# RGBstrip-ESP07-Controller-Amp-V1_2.net
KiCad netlist of a schematic drawn in EAGLE
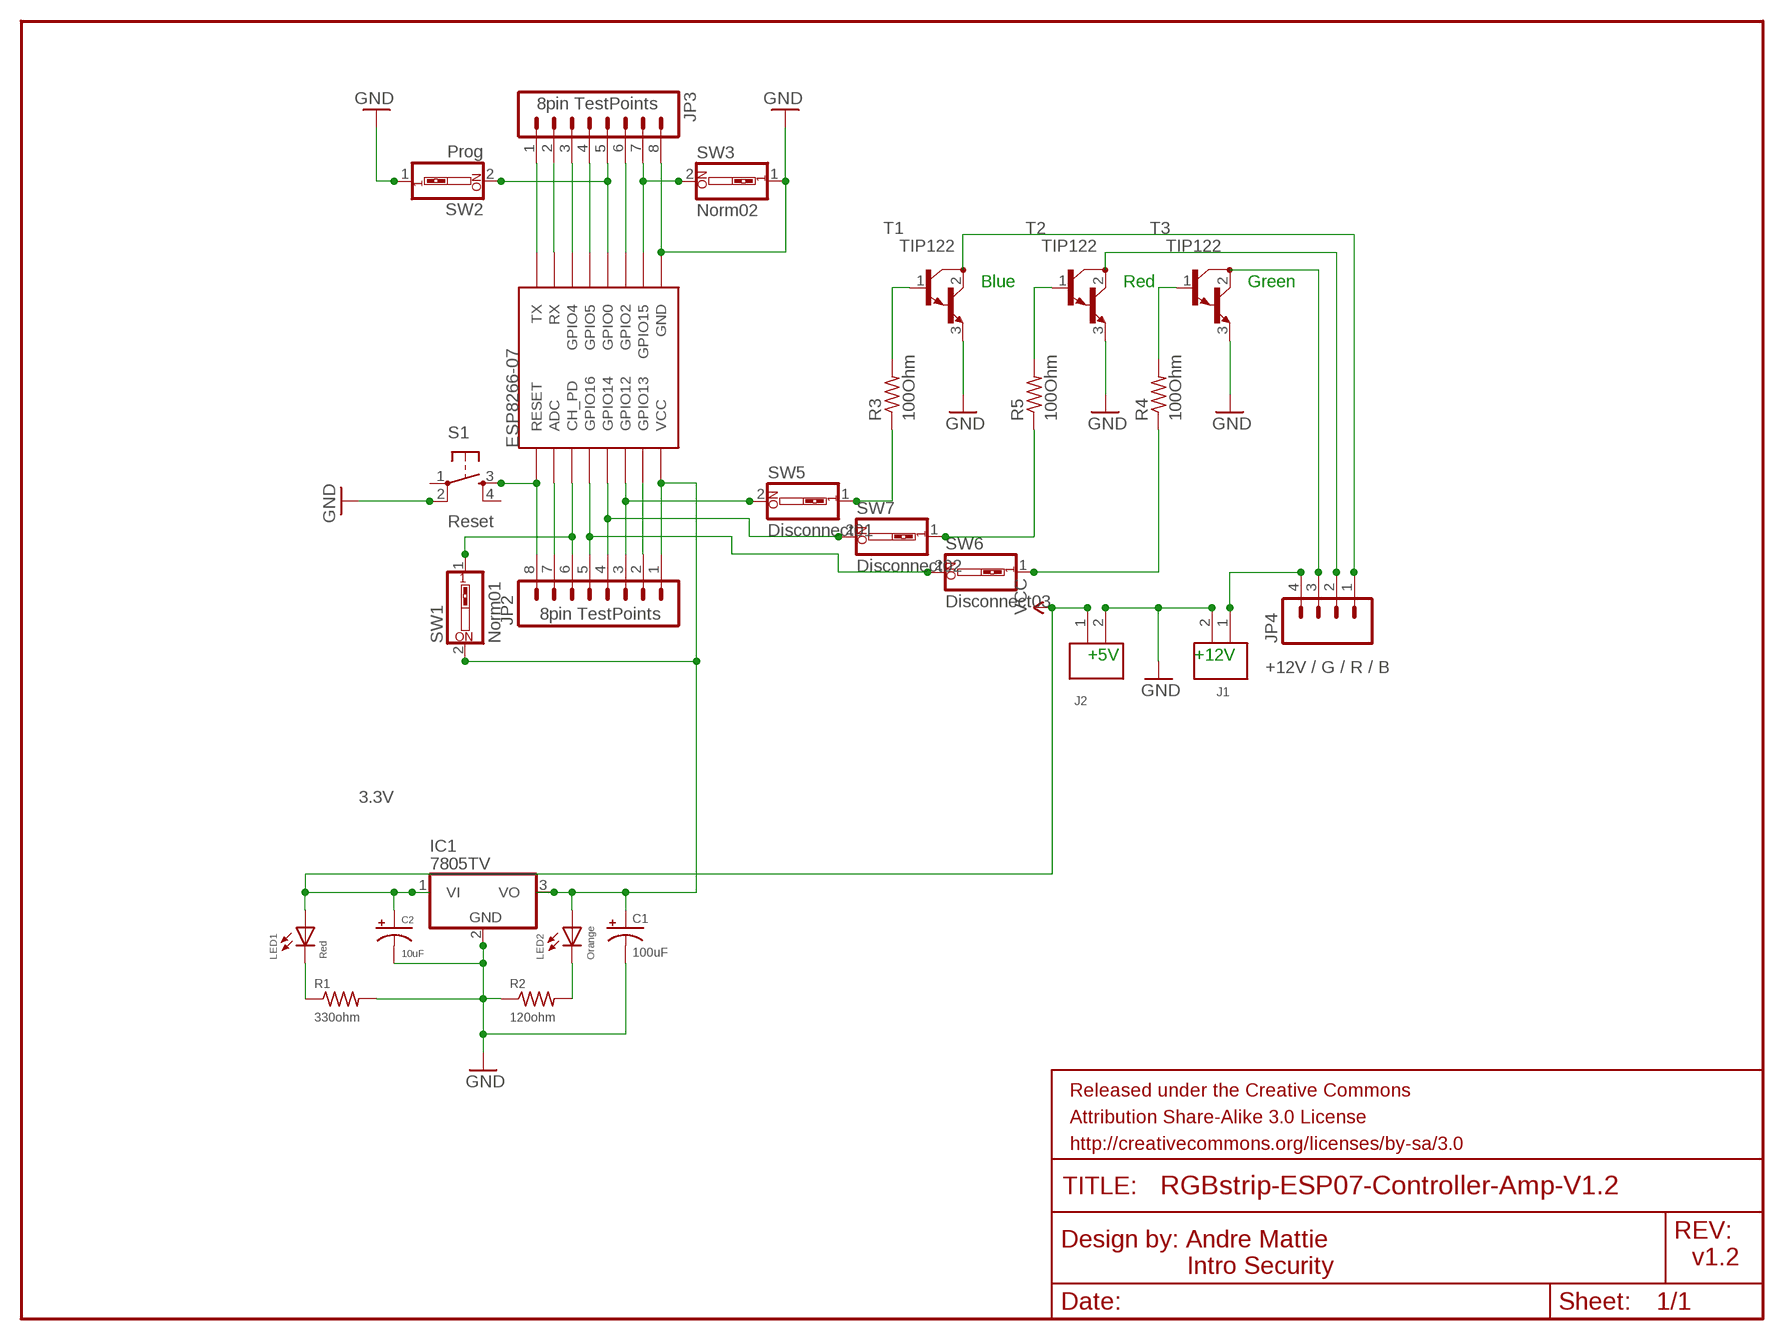
[diagram p0: schematic, sheet 1]

(export (version "E")
  (design (tool "Eeschema 10.0.6"))
  (components
    (comp (ref "C1")
      (value "100uF")
      (footprint "eagle-import:CPOL-RADIAL-100UF-25V")
      (libsource (lib "eagle-import") (part "CAP_POLPTH1"))
    )
    (comp (ref "C2")
      (value "10uF")
      (footprint "eagle-import:CPOL-RADIAL-10UF-25V")
      (libsource (lib "eagle-import") (part "CAP_POLPTH2"))
    )
    (comp (ref "ESP8266-07")
      (value "ESP07-16PINBOTTOM")
      (footprint "eagle-import:ESP07-16PIN")
      (libsource (lib "eagle-import") (part "ESP07-16PINBOTTOM"))
    )
    (comp (ref "FRAME1")
      (value "FRAME-LETTER")
      (footprint "eagle-import:CREATIVE_COMMONS")
      (libsource (lib "eagle-import") (part "FRAME-LETTER"))
    )
    (comp (ref "IC1")
      (value "7805TV")
      (footprint "eagle-import:TO220V")
      (libsource (lib "eagle-import") (part "78TV05"))
    )
    (comp (ref "J1")
      (value "SCREW-TERMINAL_2_0.100")
      (footprint "eagle-import:CONN_BLOCK_2")
      (libsource (lib "eagle-import") (part "SCREW-TERMINAL_2_0.100"))
    )
    (comp (ref "J2")
      (value "SCREW-TERMINAL_2_0.100")
      (footprint "eagle-import:CONN_BLOCK_2")
      (libsource (lib "eagle-import") (part "SCREW-TERMINAL_2_0.100"))
    )
    (comp (ref "JP2")
      (value "8pin TestPoints")
      (footprint "eagle-import:1X08_LONGPADS")
      (libsource (lib "eagle-import") (part "M08LONGPADS"))
    )
    (comp (ref "JP3")
      (value "8pin TestPoints")
      (footprint "eagle-import:1X08_LONGPADS")
      (libsource (lib "eagle-import") (part "M08LONGPADS"))
    )
    (comp (ref "JP4")
      (value "+12V / G / R / B")
      (footprint "eagle-import:1X04_LONGPADS")
      (libsource (lib "eagle-import") (part "M04LONGPADS"))
    )
    (comp (ref "LED1")
      (value "Red")
      (footprint "eagle-import:LED3MM")
      (libsource (lib "eagle-import") (part "LED3MM"))
    )
    (comp (ref "LED2")
      (value "Orange")
      (footprint "eagle-import:LED3MM")
      (libsource (lib "eagle-import") (part "LED3MM"))
    )
    (comp (ref "R1")
      (value "330ohm")
      (footprint "eagle-import:0309V")
      (libsource (lib "eagle-import") (part "R-US_0309/V"))
    )
    (comp (ref "R2")
      (value "120ohm")
      (footprint "eagle-import:0309V")
      (libsource (lib "eagle-import") (part "R-US_0309/V"))
    )
    (comp (ref "R3")
      (value "100Ohm")
      (footprint "eagle-import:0309V")
      (libsource (lib "eagle-import") (part "R-US_0309/V"))
    )
    (comp (ref "R4")
      (value "100Ohm")
      (footprint "eagle-import:0309V")
      (libsource (lib "eagle-import") (part "R-US_0309/V"))
    )
    (comp (ref "R5")
      (value "100Ohm")
      (footprint "eagle-import:0309V")
      (libsource (lib "eagle-import") (part "R-US_0309/V"))
    )
    (comp (ref "S1")
      (value "Reset")
      (footprint "eagle-import:TACTILE-PTH")
      (libsource (lib "eagle-import") (part "TAC_SWITCHPTH"))
    )
    (comp (ref "SW1")
      (value "Norm01")
      (footprint "eagle-import:EDG-01")
      (libsource (lib "eagle-import") (part "SW_DIP-1"))
    )
    (comp (ref "SW2")
      (value "Prog")
      (footprint "eagle-import:EDG-01")
      (libsource (lib "eagle-import") (part "SW_DIP-1"))
    )
    (comp (ref "SW3")
      (value "Norm02")
      (footprint "eagle-import:EDG-01")
      (libsource (lib "eagle-import") (part "SW_DIP-1"))
    )
    (comp (ref "SW5")
      (value "Disconnect01")
      (footprint "eagle-import:EDG-01")
      (libsource (lib "eagle-import") (part "SW_DIP-1"))
    )
    (comp (ref "SW6")
      (value "Disconnect03")
      (footprint "eagle-import:EDG-01")
      (libsource (lib "eagle-import") (part "SW_DIP-1"))
    )
    (comp (ref "SW7")
      (value "Disconnect02")
      (footprint "eagle-import:EDG-01")
      (libsource (lib "eagle-import") (part "SW_DIP-1"))
    )
    (comp (ref "T1")
      (value "TIP122")
      (footprint "eagle-import:TO220")
      (libsource (lib "eagle-import") (part "TIP122"))
    )
    (comp (ref "T2")
      (value "TIP122")
      (footprint "eagle-import:TO220")
      (libsource (lib "eagle-import") (part "TIP122"))
    )
    (comp (ref "T3")
      (value "TIP122")
      (footprint "eagle-import:TO220")
      (libsource (lib "eagle-import") (part "TIP122"))
    )
  )
  (nets
    (net (code "1") (name "/3.3V") (class "Default")
      (node (ref "C1") (pin "1") (pinfunction "+_1") (pintype "passive"))
      (node (ref "ESP8266-07") (pin "VCC") (pinfunction "VCC_VCC") (pintype "bidirectional"))
      (node (ref "IC1") (pin "3") (pinfunction "VO_3") (pintype "passive"))
      (node (ref "JP2") (pin "1") (pinfunction "1_1") (pintype "passive"))
      (node (ref "LED2") (pin "A") (pinfunction "A_A") (pintype "passive"))
      (node (ref "SW1") (pin "2") (pinfunction "2_2") (pintype "passive"))
    )
    (net (code "2") (name "GND") (class "Default")
      (node (ref "C1") (pin "2") (pinfunction "-_2") (pintype "passive"))
      (node (ref "C2") (pin "2") (pinfunction "-_2") (pintype "passive"))
      (node (ref "ESP8266-07") (pin "GND") (pinfunction "GND_GND") (pintype "bidirectional"))
      (node (ref "IC1") (pin "2") (pinfunction "GND_2") (pintype "passive"))
      (node (ref "J1") (pin "2") (pinfunction "2_2") (pintype "bidirectional"))
      (node (ref "J2") (pin "2") (pinfunction "2_2") (pintype "bidirectional"))
      (node (ref "JP3") (pin "8") (pinfunction "8_8") (pintype "passive"))
      (node (ref "R1") (pin "2") (pinfunction "2_2") (pintype "passive"))
      (node (ref "R2") (pin "1") (pinfunction "1_1") (pintype "passive"))
      (node (ref "S1") (pin "2") (pinfunction "2_2") (pintype "passive"))
      (node (ref "SW2") (pin "1") (pinfunction "1_1") (pintype "passive"))
      (node (ref "SW3") (pin "1") (pinfunction "1_1") (pintype "passive"))
      (node (ref "T1") (pin "3") (pinfunction "E_3") (pintype "passive"))
      (node (ref "T2") (pin "3") (pinfunction "E_3") (pintype "passive"))
      (node (ref "T3") (pin "3") (pinfunction "E_3") (pintype "passive"))
    )
    (net (code "3") (name "Net-(ESP8266-07-PadADC)") (class "Default")
      (node (ref "ESP8266-07") (pin "ADC") (pinfunction "ADC_ADC") (pintype "bidirectional"))
      (node (ref "JP2") (pin "7") (pinfunction "7_7") (pintype "passive"))
    )
    (net (code "4") (name "Net-(ESP8266-07-PadCH_PD)") (class "Default")
      (node (ref "ESP8266-07") (pin "CH_PD") (pinfunction "CH_PD_CH_PD") (pintype "bidirectional"))
      (node (ref "JP2") (pin "6") (pinfunction "6_6") (pintype "passive"))
      (node (ref "SW1") (pin "1") (pinfunction "1_1") (pintype "passive"))
    )
    (net (code "5") (name "Net-(ESP8266-07-PadGPIO0)") (class "Default")
      (node (ref "ESP8266-07") (pin "GPIO0") (pinfunction "GPIO0_GPIO0") (pintype "bidirectional"))
      (node (ref "JP3") (pin "5") (pinfunction "5_5") (pintype "passive"))
      (node (ref "SW2") (pin "2") (pinfunction "2_2") (pintype "passive"))
    )
    (net (code "6") (name "Net-(ESP8266-07-PadGPIO2)") (class "Default")
      (node (ref "ESP8266-07") (pin "GPIO2") (pinfunction "GPIO2_GPIO2") (pintype "bidirectional"))
      (node (ref "JP3") (pin "6") (pinfunction "6_6") (pintype "passive"))
    )
    (net (code "7") (name "Net-(ESP8266-07-PadGPIO4)") (class "Default")
      (node (ref "ESP8266-07") (pin "GPIO4") (pinfunction "GPIO4_GPIO4") (pintype "bidirectional"))
      (node (ref "JP3") (pin "3") (pinfunction "3_3") (pintype "passive"))
    )
    (net (code "8") (name "Net-(ESP8266-07-PadGPIO5)") (class "Default")
      (node (ref "ESP8266-07") (pin "GPIO5") (pinfunction "GPIO5_GPIO5") (pintype "bidirectional"))
      (node (ref "JP3") (pin "4") (pinfunction "4_4") (pintype "passive"))
    )
    (net (code "9") (name "Net-(ESP8266-07-PadGPIO12)") (class "Default")
      (node (ref "ESP8266-07") (pin "GPIO12") (pinfunction "GPIO12_GPIO12") (pintype "bidirectional"))
      (node (ref "JP2") (pin "3") (pinfunction "3_3") (pintype "passive"))
      (node (ref "SW5") (pin "2") (pinfunction "2_2") (pintype "passive"))
    )
    (net (code "10") (name "Net-(ESP8266-07-PadGPIO13)") (class "Default")
      (node (ref "ESP8266-07") (pin "GPIO13") (pinfunction "GPIO13_GPIO13") (pintype "bidirectional"))
      (node (ref "JP2") (pin "2") (pinfunction "2_2") (pintype "passive"))
    )
    (net (code "11") (name "Net-(ESP8266-07-PadGPIO14)") (class "Default")
      (node (ref "ESP8266-07") (pin "GPIO14") (pinfunction "GPIO14_GPIO14") (pintype "bidirectional"))
      (node (ref "JP2") (pin "4") (pinfunction "4_4") (pintype "passive"))
      (node (ref "SW7") (pin "2") (pinfunction "2_2") (pintype "passive"))
    )
    (net (code "12") (name "Net-(ESP8266-07-PadGPIO15)") (class "Default")
      (node (ref "ESP8266-07") (pin "GPIO15") (pinfunction "GPIO15_GPIO15") (pintype "bidirectional"))
      (node (ref "JP3") (pin "7") (pinfunction "7_7") (pintype "passive"))
      (node (ref "SW3") (pin "2") (pinfunction "2_2") (pintype "passive"))
    )
    (net (code "13") (name "Net-(ESP8266-07-PadGPIO16)") (class "Default")
      (node (ref "ESP8266-07") (pin "GPIO16") (pinfunction "GPIO16_GPIO16") (pintype "bidirectional"))
      (node (ref "JP2") (pin "5") (pinfunction "5_5") (pintype "passive"))
      (node (ref "SW6") (pin "2") (pinfunction "2_2") (pintype "passive"))
    )
    (net (code "14") (name "Net-(ESP8266-07-PadRX)") (class "Default")
      (node (ref "ESP8266-07") (pin "RX") (pinfunction "RX_RX") (pintype "bidirectional"))
      (node (ref "JP3") (pin "2") (pinfunction "2_2") (pintype "passive"))
    )
    (net (code "15") (name "Net-(ESP8266-07-PadTX)") (class "Default")
      (node (ref "ESP8266-07") (pin "TX") (pinfunction "TX_TX") (pintype "bidirectional"))
      (node (ref "JP3") (pin "1") (pinfunction "1_1") (pintype "passive"))
    )
    (net (code "16") (name "Net-(ESP8266-07-RESET)") (class "Default")
      (node (ref "ESP8266-07") (pin "REST") (pinfunction "RESET_REST") (pintype "bidirectional"))
      (node (ref "JP2") (pin "8") (pinfunction "8_8") (pintype "passive"))
      (node (ref "S1") (pin "3") (pinfunction "3_3") (pintype "passive"))
    )
    (net (code "17") (name "Net-(J1-Pad1)") (class "Default")
      (node (ref "J1") (pin "1") (pinfunction "1_1") (pintype "bidirectional"))
      (node (ref "JP4") (pin "4") (pinfunction "4_4") (pintype "passive"))
    )
    (net (code "18") (name "Net-(LED1-C)") (class "Default")
      (node (ref "LED1") (pin "K") (pinfunction "C_K") (pintype "passive"))
      (node (ref "R1") (pin "1") (pinfunction "1_1") (pintype "passive"))
    )
    (net (code "19") (name "Net-(LED2-C)") (class "Default")
      (node (ref "LED2") (pin "K") (pinfunction "C_K") (pintype "passive"))
      (node (ref "R2") (pin "2") (pinfunction "2_2") (pintype "passive"))
    )
    (net (code "20") (name "Net-(R3-Pad1)") (class "Default")
      (node (ref "R3") (pin "1") (pinfunction "1_1") (pintype "passive"))
      (node (ref "SW5") (pin "1") (pinfunction "1_1") (pintype "passive"))
    )
    (net (code "21") (name "Net-(R4-Pad1)") (class "Default")
      (node (ref "R4") (pin "1") (pinfunction "1_1") (pintype "passive"))
      (node (ref "SW6") (pin "1") (pinfunction "1_1") (pintype "passive"))
    )
    (net (code "22") (name "Net-(R5-Pad1)") (class "Default")
      (node (ref "R5") (pin "1") (pinfunction "1_1") (pintype "passive"))
      (node (ref "SW7") (pin "1") (pinfunction "1_1") (pintype "passive"))
    )
    (net (code "23") (name "Net-(T1-B)") (class "Default")
      (node (ref "R3") (pin "2") (pinfunction "2_2") (pintype "passive"))
      (node (ref "T1") (pin "1") (pinfunction "B_1") (pintype "passive"))
    )
    (net (code "24") (name "Net-(T1-C)") (class "Default")
      (node (ref "JP4") (pin "1") (pinfunction "1_1") (pintype "passive"))
      (node (ref "T1") (pin "2") (pinfunction "C_2") (pintype "passive"))
    )
    (net (code "25") (name "Net-(T2-B)") (class "Default")
      (node (ref "R5") (pin "2") (pinfunction "2_2") (pintype "passive"))
      (node (ref "T2") (pin "1") (pinfunction "B_1") (pintype "passive"))
    )
    (net (code "26") (name "Net-(T2-C)") (class "Default")
      (node (ref "JP4") (pin "2") (pinfunction "2_2") (pintype "passive"))
      (node (ref "T2") (pin "2") (pinfunction "C_2") (pintype "passive"))
    )
    (net (code "27") (name "Net-(T3-B)") (class "Default")
      (node (ref "R4") (pin "2") (pinfunction "2_2") (pintype "passive"))
      (node (ref "T3") (pin "1") (pinfunction "B_1") (pintype "passive"))
    )
    (net (code "28") (name "Net-(T3-C)") (class "Default")
      (node (ref "JP4") (pin "3") (pinfunction "3_3") (pintype "passive"))
      (node (ref "T3") (pin "2") (pinfunction "C_2") (pintype "passive"))
    )
    (net (code "29") (name "VCC") (class "Default")
      (node (ref "C2") (pin "1") (pinfunction "+_1") (pintype "passive"))
      (node (ref "IC1") (pin "1") (pinfunction "VI_1") (pintype "input"))
      (node (ref "J2") (pin "1") (pinfunction "1_1") (pintype "bidirectional"))
      (node (ref "LED1") (pin "A") (pinfunction "A_A") (pintype "passive"))
    )
    (net (code "30") (name "unconnected-(S1-Pad1)") (class "Default")
      (node (ref "S1") (pin "1") (pinfunction "1_1") (pintype "passive"))
    )
    (net (code "31") (name "unconnected-(S1-Pad4)") (class "Default")
      (node (ref "S1") (pin "4") (pinfunction "4_4") (pintype "passive"))
    )
  )
)
